# ne555.net
KiCad netlist of a schematic drawn in Altium Designer
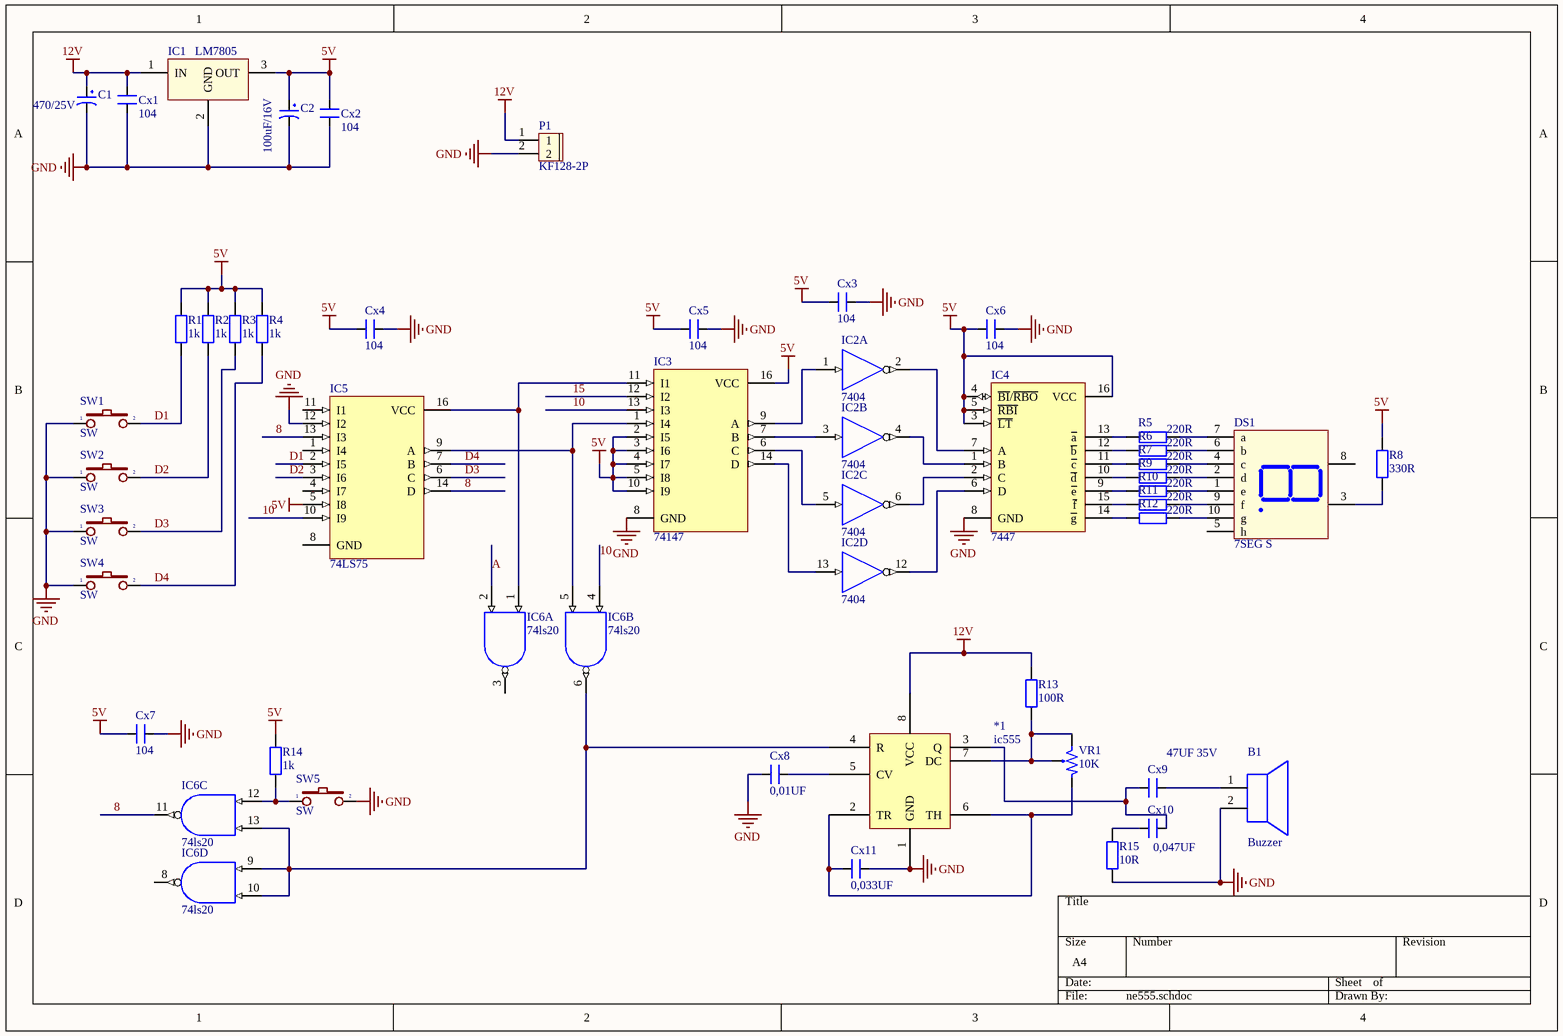
[diagram p0: ne555.schdoc]

(export (version "E")
  (design (tool "Eeschema 10.0.6"))
  (components
    (comp (ref "*1") (value "ic555") (footprint "DIP8/W0.3") (libsource (lib "sch.hien") (part "ic555")))
    (comp (ref "B1")
      (value "Buzzer")
      (footprint "MinhTien_PcbLib:Buzzer")
      (libsource (lib "MinhTien_SCHLib") (part "Buzzer"))
    )
    (comp (ref "C1")
      (value "470/25V")
      (footprint "CP1.5/3.4")
      (description "Cap 1000uF/16V - 220uF/50V")
      (libsource (lib "TERLAB") (part "CP4"))
    )
    (comp (ref "C2")
      (value "100uF/16V")
      (footprint "CP1.5/3.4")
      (description "Cap 1000uF/16V - 220uF/50V")
      (libsource (lib "TERLAB") (part "CP4"))
    )
    (comp (ref "Cx1")
      (value "104")
      (footprint "CN1")
      (description "Cremic For Xtal 1pF => 100pF")
      (libsource (lib "TERLAB") (part "CN0"))
    )
    (comp (ref "Cx2")
      (value "104")
      (footprint "CN1")
      (description "Cremic For Xtal 1pF => 100pF")
      (libsource (lib "TERLAB") (part "CN0"))
    )
    (comp (ref "Cx3")
      (value "104")
      (footprint "CN1")
      (description "Cremic For Xtal 1pF => 100pF")
      (libsource (lib "TERLAB") (part "CN0"))
    )
    (comp (ref "Cx4")
      (value "104")
      (footprint "CN1")
      (description "Cremic For Xtal 1pF => 100pF")
      (libsource (lib "TERLAB") (part "CN0"))
    )
    (comp (ref "Cx5")
      (value "104")
      (footprint "CN1")
      (description "Cremic For Xtal 1pF => 100pF")
      (libsource (lib "TERLAB") (part "CN0"))
    )
    (comp (ref "Cx6")
      (value "104")
      (footprint "CN1")
      (description "Cremic For Xtal 1pF => 100pF")
      (libsource (lib "TERLAB") (part "CN0"))
    )
    (comp (ref "Cx7")
      (value "104")
      (footprint "CN1")
      (description "Cremic For Xtal 1pF => 100pF")
      (libsource (lib "TERLAB") (part "CN0"))
    )
    (comp (ref "Cx8")
      (value "0,01UF")
      (footprint "CN1")
      (description "Cremic For Xtal 1pF => 100pF")
      (libsource (lib "TERLAB") (part "CN0"))
    )
    (comp (ref "Cx9")
      (value "47UF 35V")
      (footprint "CN1")
      (description "Cremic For Xtal 1pF => 100pF")
      (libsource (lib "TERLAB") (part "CN0"))
    )
    (comp (ref "Cx10")
      (value "0,047UF")
      (footprint "CN1")
      (description "Cremic For Xtal 1pF => 100pF")
      (libsource (lib "TERLAB") (part "CN0"))
    )
    (comp (ref "Cx11")
      (value "0,033UF")
      (footprint "CN1")
      (description "Cremic For Xtal 1pF => 100pF")
      (libsource (lib "TERLAB") (part "CN0"))
    )
    (comp (ref "DS1")
      (value "7SEG S")
      (footprint "7SEGS")
      (description "Single 7 Seg Dipslay")
      (libsource (lib "TERLAB") (part "LED7S"))
    )
    (comp (ref "IC1")
      (value "LM7805")
      (footprint "QTO-220")
      (description "On ap +, from + 5 to + 24VDC")
      (libsource (lib "TERLAB") (part "LM78xx"))
    )
    (comp (ref "IC2")
      (value "7404")
      (footprint "DIP14/W0.3")
      (description "Hex Inverter")
      (libsource (lib "TERLAB") (part "7404"))
    )
    (comp (ref "IC3")
      (value "74147")
      (footprint "DIP16/W0.3")
      (description "10-Line to 4-Line Priority Encoder")
      (fields (field (name "COPYRIGHT BY") "VanDungEvn@Gmail.com"))
      (libsource (lib "TERLAB") (part "74147"))
    )
    (comp (ref "IC4")
      (value "7447")
      (footprint "DIP16/W0.3")
      (description "BCD to 7-Segment Decoder/Driver")
      (libsource (lib "TERLAB") (part "7447"))
    )
    (comp (ref "IC5")
      (value "74LS75")
      (footprint "DIP16/W0.3")
      (description "10-Line to 4-Line Priority Encoder")
      (fields (field (name "COPYRIGHT BY") "VanDungEvn@Gmail.com"))
      (libsource (lib "TERLAB") (part "74147"))
    )
    (comp (ref "IC6")
      (value "74ls20")
      (footprint "DIP14/W0.3")
      (description "Quad 2-Input NAND Gate")
      (fields (field (name "COPYRIGHT BY") "VanDungEvn@Gmail.com"))
      (libsource (lib "TERLAB") (part "7400"))
    )
    (comp (ref "P1")
      (value "KF128-2P")
      (footprint "con 2 kf128")
      (description "Cắm")
      (libsource (lib "SCH Chuan") (part "Con 2 kf128"))
    )
    (comp (ref "R1")
      (value "1k")
      (footprint "R1/4W")
      (description "Resistor 1/4W")
      (libsource (lib "TERLAB") (part "R1/4W"))
    )
    (comp (ref "R2")
      (value "1k")
      (footprint "R1/4W")
      (description "Resistor 1/4W")
      (libsource (lib "TERLAB") (part "R1/4W"))
    )
    (comp (ref "R3")
      (value "1k")
      (footprint "R1/4W")
      (description "Resistor 1/4W")
      (libsource (lib "TERLAB") (part "R1/4W"))
    )
    (comp (ref "R4")
      (value "1k")
      (footprint "R1/4W")
      (description "Resistor 1/4W")
      (libsource (lib "TERLAB") (part "R1/4W"))
    )
    (comp (ref "R5")
      (value "220R")
      (footprint "R1/4W")
      (description "Resistor 1/4W")
      (libsource (lib "TERLAB") (part "R1/4W"))
    )
    (comp (ref "R6")
      (value "220R")
      (footprint "R1/4W")
      (description "Resistor 1/4W")
      (libsource (lib "TERLAB") (part "R1/4W"))
    )
    (comp (ref "R7")
      (value "220R")
      (footprint "R1/4W")
      (description "Resistor 1/4W")
      (libsource (lib "TERLAB") (part "R1/4W"))
    )
    (comp (ref "R8")
      (value "330R")
      (footprint "R1/4W")
      (description "Resistor 1/4W")
      (libsource (lib "TERLAB") (part "R1/4W"))
    )
    (comp (ref "R9")
      (value "220R")
      (footprint "R1/4W")
      (description "Resistor 1/4W")
      (libsource (lib "TERLAB") (part "R1/4W"))
    )
    (comp (ref "R10")
      (value "220R")
      (footprint "R1/4W")
      (description "Resistor 1/4W")
      (libsource (lib "TERLAB") (part "R1/4W"))
    )
    (comp (ref "R11")
      (value "220R")
      (footprint "R1/4W")
      (description "Resistor 1/4W")
      (libsource (lib "TERLAB") (part "R1/4W"))
    )
    (comp (ref "R12")
      (value "220R")
      (footprint "R1/4W")
      (description "Resistor 1/4W")
      (libsource (lib "TERLAB") (part "R1/4W"))
    )
    (comp (ref "R13")
      (value "100R")
      (footprint "R1/4W")
      (description "Resistor 1/4W")
      (libsource (lib "TERLAB") (part "R1/4W"))
    )
    (comp (ref "R14")
      (value "1k")
      (footprint "R1/4W")
      (description "Resistor 1/4W")
      (libsource (lib "TERLAB") (part "R1/4W"))
    )
    (comp (ref "R15")
      (value "10R")
      (footprint "R1/4W")
      (description "Resistor 1/4W")
      (libsource (lib "TERLAB") (part "R1/4W"))
    )
    (comp (ref "SW1")
      (value "SW")
      (footprint "SW2")
      (description "Switch button 2 pin")
      (libsource (lib "TERLAB") (part "SW2"))
    )
    (comp (ref "SW2")
      (value "SW")
      (footprint "SW2")
      (description "Switch button 2 pin")
      (libsource (lib "TERLAB") (part "SW2"))
    )
    (comp (ref "SW3")
      (value "SW")
      (footprint "SW2")
      (description "Switch button 2 pin")
      (libsource (lib "TERLAB") (part "SW2"))
    )
    (comp (ref "SW4")
      (value "SW")
      (footprint "SW2")
      (description "Switch button 2 pin")
      (libsource (lib "TERLAB") (part "SW2"))
    )
    (comp (ref "SW5")
      (value "SW")
      (footprint "SW2")
      (description "Switch button 2 pin")
      (libsource (lib "TERLAB") (part "SW2"))
    )
    (comp (ref "VR1")
      (value "10K")
      (footprint "VR1")
      (description "Var Resistor")
      (libsource (lib "TERLAB") (part "VR1"))
    )
  )
  (nets
    (net (code "1") (name "/8") (class "Default")
      (node (ref "IC5") (pin "13") (pinfunction "I3_13") (pintype "input"))
      (node (ref "IC5") (pin "14") (pinfunction "D_14") (pintype "output"))
      (node (ref "IC6") (pin "11") (pinfunction "~{O}_11") (pintype "output"))
    )
    (net (code "2") (name "/10") (class "Default")
      (node (ref "IC3") (pin "13") (pinfunction "I3_13") (pintype "input"))
      (node (ref "IC5") (pin "10") (pinfunction "I9_10") (pintype "input"))
      (node (ref "IC6") (pin "4") (pinfunction "A_4") (pintype "input"))
    )
    (net (code "3") (name "/15") (class "Default")
      (node (ref "IC3") (pin "12") (pinfunction "I2_12") (pintype "input"))
    )
    (net (code "4") (name "/A") (class "Default")
      (node (ref "IC6") (pin "2") (pinfunction "B_2") (pintype "input"))
    )
    (net (code "5") (name "/D1") (class "Default")
      (node (ref "IC5") (pin "2") (pinfunction "I5_2") (pintype "input"))
      (node (ref "R1") (pin "1") (pinfunction "1_1") (pintype "passive"))
      (node (ref "SW1") (pin "2") (pinfunction "2_2") (pintype "passive"))
    )
    (net (code "6") (name "/D2") (class "Default")
      (node (ref "IC5") (pin "3") (pinfunction "I6_3") (pintype "input"))
      (node (ref "R2") (pin "1") (pinfunction "1_1") (pintype "passive"))
      (node (ref "SW2") (pin "2") (pinfunction "2_2") (pintype "passive"))
    )
    (net (code "7") (name "/D3") (class "Default")
      (node (ref "IC5") (pin "6") (pinfunction "C_6") (pintype "output"))
      (node (ref "R3") (pin "1") (pinfunction "1_1") (pintype "passive"))
      (node (ref "SW3") (pin "2") (pinfunction "2_2") (pintype "passive"))
    )
    (net (code "8") (name "/D4") (class "Default")
      (node (ref "IC5") (pin "7") (pinfunction "B_7") (pintype "output"))
      (node (ref "R4") (pin "1") (pinfunction "1_1") (pintype "passive"))
      (node (ref "SW4") (pin "2") (pinfunction "2_2") (pintype "passive"))
    )
    (net (code "9") (name "5V") (class "Default")
      (node (ref "C2") (pin "1") (pinfunction "1_1") (pintype "passive"))
      (node (ref "Cx2") (pin "2") (pinfunction "2_2") (pintype "passive"))
      (node (ref "Cx3") (pin "2") (pinfunction "2_2") (pintype "passive"))
      (node (ref "Cx4") (pin "2") (pinfunction "2_2") (pintype "passive"))
      (node (ref "Cx5") (pin "2") (pinfunction "2_2") (pintype "passive"))
      (node (ref "Cx6") (pin "2") (pinfunction "2_2") (pintype "passive"))
      (node (ref "Cx7") (pin "2") (pinfunction "2_2") (pintype "passive"))
      (node (ref "IC1") (pin "3") (pinfunction "OUT_3") (pintype "passive"))
      (node (ref "IC3") (pin "10") (pinfunction "I9_10") (pintype "input"))
      (node (ref "IC3") (pin "16") (pinfunction "VCC_16") (pintype "power_in"))
      (node (ref "IC3") (pin "2") (pinfunction "I5_2") (pintype "input"))
      (node (ref "IC3") (pin "3") (pinfunction "I6_3") (pintype "input"))
      (node (ref "IC3") (pin "4") (pinfunction "I7_4") (pintype "input"))
      (node (ref "IC3") (pin "5") (pinfunction "I8_5") (pintype "input"))
      (node (ref "IC4") (pin "16") (pinfunction "VCC_16") (pintype "power_in"))
      (node (ref "IC4") (pin "3") (pinfunction "~{LT}_3") (pintype "input"))
      (node (ref "IC4") (pin "4") (pinfunction "~{BI}/~{RBO}_4") (pintype "bidirectional"))
      (node (ref "IC4") (pin "5") (pinfunction "~{RBI}_5") (pintype "input"))
      (node (ref "IC5") (pin "5") (pinfunction "I8_5") (pintype "input"))
      (node (ref "R1") (pin "2") (pinfunction "2_2") (pintype "passive"))
      (node (ref "R14") (pin "2") (pinfunction "2_2") (pintype "passive"))
      (node (ref "R2") (pin "2") (pinfunction "2_2") (pintype "passive"))
      (node (ref "R3") (pin "2") (pinfunction "2_2") (pintype "passive"))
      (node (ref "R4") (pin "2") (pinfunction "2_2") (pintype "passive"))
      (node (ref "R8") (pin "2") (pinfunction "2_2") (pintype "passive"))
    )
    (net (code "10") (name "12V") (class "Default")
      (node (ref "*1") (pin "8") (pinfunction "VCC_8") (pintype "passive"))
      (node (ref "C1") (pin "1") (pinfunction "1_1") (pintype "passive"))
      (node (ref "Cx1") (pin "2") (pinfunction "2_2") (pintype "passive"))
      (node (ref "IC1") (pin "1") (pinfunction "IN_1") (pintype "passive"))
      (node (ref "P1") (pin "1") (pinfunction "1_1") (pintype "passive"))
      (node (ref "R13") (pin "2") (pinfunction "2_2") (pintype "passive"))
    )
    (net (code "11") (name "GND") (class "Default")
      (node (ref "*1") (pin "1") (pinfunction "GND_1") (pintype "passive"))
      (node (ref "B1") (pin "2") (pinfunction "-_2") (pintype "passive"))
      (node (ref "C1") (pin "2") (pinfunction "2_2") (pintype "passive"))
      (node (ref "C2") (pin "2") (pinfunction "2_2") (pintype "passive"))
      (node (ref "Cx1") (pin "1") (pinfunction "1_1") (pintype "passive"))
      (node (ref "Cx11") (pin "1") (pinfunction "1_1") (pintype "passive"))
      (node (ref "Cx2") (pin "1") (pinfunction "1_1") (pintype "passive"))
      (node (ref "Cx3") (pin "1") (pinfunction "1_1") (pintype "passive"))
      (node (ref "Cx4") (pin "1") (pinfunction "1_1") (pintype "passive"))
      (node (ref "Cx5") (pin "1") (pinfunction "1_1") (pintype "passive"))
      (node (ref "Cx6") (pin "1") (pinfunction "1_1") (pintype "passive"))
      (node (ref "Cx7") (pin "1") (pinfunction "1_1") (pintype "passive"))
      (node (ref "Cx8") (pin "2") (pinfunction "2_2") (pintype "passive"))
      (node (ref "IC1") (pin "2") (pinfunction "GND_2") (pintype "passive"))
      (node (ref "IC2") (pin "7") (pinfunction "GND_7") (pintype "power_in"))
      (node (ref "IC3") (pin "8") (pinfunction "GND_8") (pintype "power_in"))
      (node (ref "IC4") (pin "8") (pinfunction "GND_8") (pintype "power_in"))
      (node (ref "IC5") (pin "12") (pinfunction "I2_12") (pintype "input"))
      (node (ref "IC6") (pin "7") (pinfunction "GND_7") (pintype "power_in"))
      (node (ref "P1") (pin "2") (pinfunction "2_2") (pintype "passive"))
      (node (ref "R15") (pin "1") (pinfunction "1_1") (pintype "passive"))
      (node (ref "SW1") (pin "1") (pinfunction "1_1") (pintype "passive"))
      (node (ref "SW2") (pin "1") (pinfunction "1_1") (pintype "passive"))
      (node (ref "SW3") (pin "1") (pinfunction "1_1") (pintype "passive"))
      (node (ref "SW4") (pin "1") (pinfunction "1_1") (pintype "passive"))
      (node (ref "SW5") (pin "2") (pinfunction "2_2") (pintype "passive"))
    )
    (net (code "12") (name "Net-(*1-CV)") (class "Default")
      (node (ref "*1") (pin "5") (pinfunction "CV_5") (pintype "passive"))
      (node (ref "Cx8") (pin "1") (pinfunction "1_1") (pintype "passive"))
    )
    (net (code "13") (name "Net-(*1-DC)") (class "Default")
      (node (ref "*1") (pin "7") (pinfunction "DC_7") (pintype "passive"))
      (node (ref "R13") (pin "1") (pinfunction "1_1") (pintype "passive"))
      (node (ref "VR1") (pin "2") (pinfunction "2_2") (pintype "passive"))
      (node (ref "VR1") (pin "3") (pinfunction "3_3") (pintype "passive"))
    )
    (net (code "14") (name "Net-(*1-Q)") (class "Default")
      (node (ref "*1") (pin "3") (pinfunction "Q_3") (pintype "passive"))
      (node (ref "Cx10") (pin "2") (pinfunction "2_2") (pintype "passive"))
      (node (ref "Cx9") (pin "1") (pinfunction "1_1") (pintype "passive"))
    )
    (net (code "15") (name "Net-(*1-R)") (class "Default")
      (node (ref "*1") (pin "4") (pinfunction "R_4") (pintype "passive"))
      (node (ref "IC6") (pin "10") (pinfunction "A_10") (pintype "input"))
      (node (ref "IC6") (pin "13") (pinfunction "A_13") (pintype "input"))
      (node (ref "IC6") (pin "6") (pinfunction "~{O}_6") (pintype "output"))
      (node (ref "IC6") (pin "9") (pinfunction "B_9") (pintype "input"))
    )
    (net (code "16") (name "Net-(*1-TH)") (class "Default")
      (node (ref "*1") (pin "2") (pinfunction "TR_2") (pintype "passive"))
      (node (ref "*1") (pin "6") (pinfunction "TH_6") (pintype "passive"))
      (node (ref "Cx11") (pin "2") (pinfunction "2_2") (pintype "passive"))
      (node (ref "VR1") (pin "1") (pinfunction "1_1") (pintype "passive"))
    )
    (net (code "17") (name "Net-(B1-+)") (class "Default")
      (node (ref "B1") (pin "1") (pinfunction "+_1") (pintype "passive"))
      (node (ref "Cx9") (pin "2") (pinfunction "2_2") (pintype "passive"))
    )
    (net (code "18") (name "Net-(Cx10-Pad1)") (class "Default")
      (node (ref "Cx10") (pin "1") (pinfunction "1_1") (pintype "passive"))
      (node (ref "R15") (pin "2") (pinfunction "2_2") (pintype "passive"))
    )
    (net (code "19") (name "Net-(DS1-Vcc-Pad3)") (class "Default")
      (node (ref "DS1") (pin "3") (pinfunction "Vcc_3") (pintype "passive"))
      (node (ref "R8") (pin "1") (pinfunction "1_1") (pintype "passive"))
    )
    (net (code "20") (name "Net-(DS1-a)") (class "Default")
      (node (ref "DS1") (pin "7") (pinfunction "a_7") (pintype "passive"))
      (node (ref "R5") (pin "2") (pinfunction "2_2") (pintype "passive"))
    )
    (net (code "21") (name "Net-(DS1-b)") (class "Default")
      (node (ref "DS1") (pin "6") (pinfunction "b_6") (pintype "passive"))
      (node (ref "R6") (pin "2") (pinfunction "2_2") (pintype "passive"))
    )
    (net (code "22") (name "Net-(DS1-c)") (class "Default")
      (node (ref "DS1") (pin "4") (pinfunction "c_4") (pintype "passive"))
      (node (ref "R7") (pin "2") (pinfunction "2_2") (pintype "passive"))
    )
    (net (code "23") (name "Net-(DS1-d)") (class "Default")
      (node (ref "DS1") (pin "2") (pinfunction "d_2") (pintype "passive"))
      (node (ref "R9") (pin "2") (pinfunction "2_2") (pintype "passive"))
    )
    (net (code "24") (name "Net-(DS1-e)") (class "Default")
      (node (ref "DS1") (pin "1") (pinfunction "e_1") (pintype "passive"))
      (node (ref "R10") (pin "2") (pinfunction "2_2") (pintype "passive"))
    )
    (net (code "25") (name "Net-(DS1-f)") (class "Default")
      (node (ref "DS1") (pin "9") (pinfunction "f_9") (pintype "passive"))
      (node (ref "R11") (pin "2") (pinfunction "2_2") (pintype "passive"))
    )
    (net (code "26") (name "Net-(DS1-g)") (class "Default")
      (node (ref "DS1") (pin "10") (pinfunction "g_10") (pintype "passive"))
      (node (ref "R12") (pin "2") (pinfunction "2_2") (pintype "passive"))
    )
    (net (code "27") (name "Net-(IC2A-A)") (class "Default")
      (node (ref "IC2") (pin "1") (pinfunction "A_1") (pintype "input"))
      (node (ref "IC3") (pin "9") (pinfunction "A_9") (pintype "output"))
    )
    (net (code "28") (name "Net-(IC2A-~{O})") (class "Default")
      (node (ref "IC2") (pin "2") (pinfunction "~{O}_2") (pintype "output"))
      (node (ref "IC4") (pin "7") (pinfunction "A_7") (pintype "input"))
    )
    (net (code "29") (name "Net-(IC2B-A)") (class "Default")
      (node (ref "IC2") (pin "3") (pinfunction "A_3") (pintype "input"))
      (node (ref "IC3") (pin "7") (pinfunction "B_7") (pintype "output"))
    )
    (net (code "30") (name "Net-(IC2B-~{O})") (class "Default")
      (node (ref "IC2") (pin "4") (pinfunction "~{O}_4") (pintype "output"))
      (node (ref "IC4") (pin "1") (pinfunction "B_1") (pintype "input"))
    )
    (net (code "31") (name "Net-(IC2C-A)") (class "Default")
      (node (ref "IC2") (pin "5") (pinfunction "A_5") (pintype "input"))
      (node (ref "IC3") (pin "6") (pinfunction "C_6") (pintype "output"))
    )
    (net (code "32") (name "Net-(IC2C-~{O})") (class "Default")
      (node (ref "IC2") (pin "6") (pinfunction "~{O}_6") (pintype "output"))
      (node (ref "IC4") (pin "2") (pinfunction "C_2") (pintype "input"))
    )
    (net (code "33") (name "Net-(IC2D-A)") (class "Default")
      (node (ref "IC2") (pin "13") (pinfunction "A_13") (pintype "input"))
      (node (ref "IC3") (pin "14") (pinfunction "D_14") (pintype "output"))
    )
    (net (code "34") (name "Net-(IC2D-~{O})") (class "Default")
      (node (ref "IC2") (pin "12") (pinfunction "~{O}_12") (pintype "output"))
      (node (ref "IC4") (pin "6") (pinfunction "D_6") (pintype "input"))
    )
    (net (code "35") (name "Net-(IC3-I1)") (class "Default")
      (node (ref "IC3") (pin "11") (pinfunction "I1_11") (pintype "input"))
      (node (ref "IC5") (pin "16") (pinfunction "VCC_16") (pintype "power_in"))
      (node (ref "IC6") (pin "1") (pinfunction "A_1") (pintype "input"))
    )
    (net (code "36") (name "Net-(IC3-I4)") (class "Default")
      (node (ref "IC3") (pin "1") (pinfunction "I4_1") (pintype "input"))
      (node (ref "IC5") (pin "9") (pinfunction "A_9") (pintype "output"))
      (node (ref "IC6") (pin "5") (pinfunction "B_5") (pintype "input"))
    )
    (net (code "37") (name "Net-(IC4-~{a})") (class "Default")
      (node (ref "IC4") (pin "13") (pinfunction "~{a}_13") (pintype "open_collector"))
      (node (ref "R5") (pin "1") (pinfunction "1_1") (pintype "passive"))
    )
    (net (code "38") (name "Net-(IC4-~{b})") (class "Default")
      (node (ref "IC4") (pin "12") (pinfunction "~{b}_12") (pintype "open_collector"))
      (node (ref "R6") (pin "1") (pinfunction "1_1") (pintype "passive"))
    )
    (net (code "39") (name "Net-(IC4-~{c})") (class "Default")
      (node (ref "IC4") (pin "11") (pinfunction "~{c}_11") (pintype "open_collector"))
      (node (ref "R7") (pin "1") (pinfunction "1_1") (pintype "passive"))
    )
    (net (code "40") (name "Net-(IC4-~{d})") (class "Default")
      (node (ref "IC4") (pin "10") (pinfunction "~{d}_10") (pintype "open_collector"))
      (node (ref "R9") (pin "1") (pinfunction "1_1") (pintype "passive"))
    )
    (net (code "41") (name "Net-(IC4-~{e})") (class "Default")
      (node (ref "IC4") (pin "9") (pinfunction "~{e}_9") (pintype "open_collector"))
      (node (ref "R10") (pin "1") (pinfunction "1_1") (pintype "passive"))
    )
    (net (code "42") (name "Net-(IC4-~{f})") (class "Default")
      (node (ref "IC4") (pin "15") (pinfunction "~{f}_15") (pintype "open_collector"))
      (node (ref "R11") (pin "1") (pinfunction "1_1") (pintype "passive"))
    )
    (net (code "43") (name "Net-(IC4-~{g})") (class "Default")
      (node (ref "IC4") (pin "14") (pinfunction "~{g}_14") (pintype "open_collector"))
      (node (ref "R12") (pin "1") (pinfunction "1_1") (pintype "passive"))
    )
    (net (code "44") (name "Net-(IC6C-B)") (class "Default")
      (node (ref "IC6") (pin "12") (pinfunction "B_12") (pintype "input"))
      (node (ref "R14") (pin "1") (pinfunction "1_1") (pintype "passive"))
      (node (ref "SW5") (pin "1") (pinfunction "1_1") (pintype "passive"))
    )
    (net (code "45") (name "VCC") (class "Default")
      (node (ref "IC2") (pin "14") (pinfunction "VCC_14") (pintype "power_in"))
      (node (ref "IC6") (pin "14") (pinfunction "VCC_14") (pintype "power_in"))
    )
    (net (code "46") (name "unconnected-(DS1-Vcc-Pad8)") (class "Default")
      (node (ref "DS1") (pin "8") (pinfunction "Vcc_8") (pintype "passive"))
    )
    (net (code "47") (name "unconnected-(DS1-h-Pad5)") (class "Default")
      (node (ref "DS1") (pin "5") (pinfunction "h_5") (pintype "passive"))
    )
    (net (code "48") (name "unconnected-(IC5-GND-Pad8)") (class "Default")
      (node (ref "IC5") (pin "8") (pinfunction "GND_8") (pintype "power_in"))
    )
    (net (code "49") (name "unconnected-(IC5-I1-Pad11)") (class "Default")
      (node (ref "IC5") (pin "11") (pinfunction "I1_11") (pintype "input"))
    )
    (net (code "50") (name "unconnected-(IC5-I4-Pad1)") (class "Default")
      (node (ref "IC5") (pin "1") (pinfunction "I4_1") (pintype "input"))
    )
    (net (code "51") (name "unconnected-(IC5-I7-Pad4)") (class "Default")
      (node (ref "IC5") (pin "4") (pinfunction "I7_4") (pintype "input"))
    )
    (net (code "52") (name "unconnected-(IC6A-~{O}-Pad3)") (class "Default")
      (node (ref "IC6") (pin "3") (pinfunction "~{O}_3") (pintype "output"))
    )
    (net (code "53") (name "unconnected-(IC6D-~{O}-Pad8)") (class "Default")
      (node (ref "IC6") (pin "8") (pinfunction "~{O}_8") (pintype "output"))
    )
  )
)
